# LV_cutoff.net
KiCad netlist of a schematic drawn in EAGLE
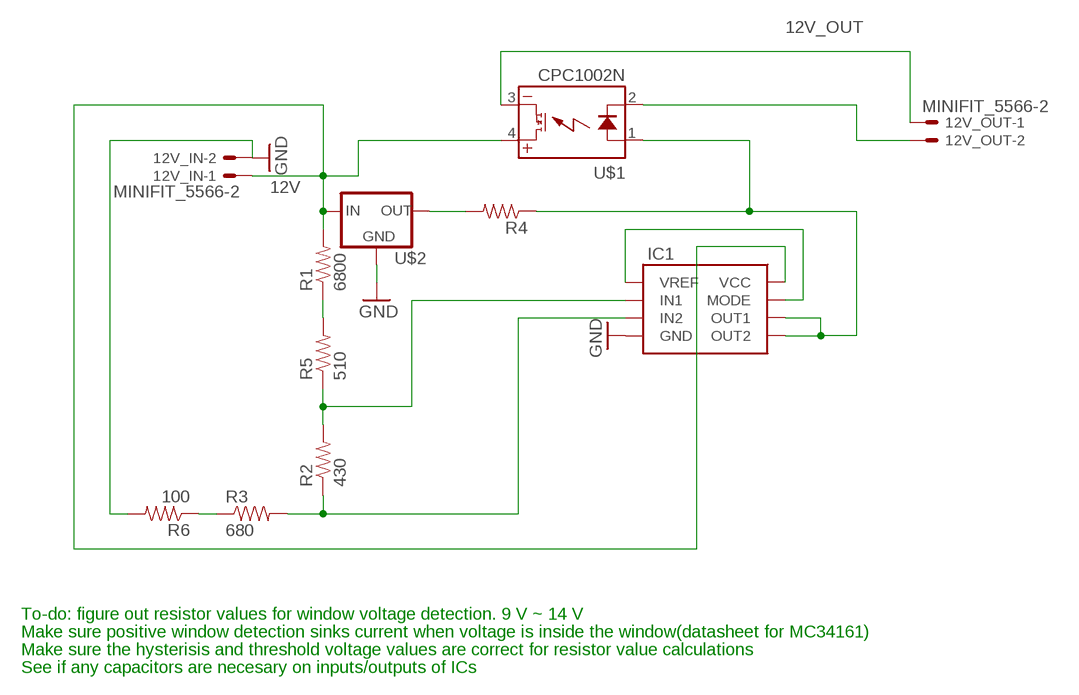
[diagram p0: schematic, sheet 1]

(export (version "E")
  (design (tool "Eeschema 10.0.6"))
  (components
    (comp (ref "12V_IN")
      (value "MINIFIT_5566-2")
      (footprint "eagle-import:MINIFIT_5566-2")
      (libsource (lib "eagle-import") (part "MINIFIT_5566-2"))
    )
    (comp (ref "12V_OUT")
      (value "MINIFIT_5566-2")
      (footprint "eagle-import:MINIFIT_5566-2")
      (libsource (lib "eagle-import") (part "MINIFIT_5566-2"))
    )
    (comp (ref "IC1")
      (value "MC34161DG")
      (footprint "eagle-import:SOIC-08")
      (libsource (lib "eagle-import") (part "MC34161DG"))
    )
    (comp (ref "R1")
      (value "6800")
      (footprint "eagle-import:0805")
      (libsource (lib "eagle-import") (part "RESISTOR0805-RES"))
    )
    (comp (ref "R2")
      (value "430")
      (footprint "eagle-import:0805")
      (libsource (lib "eagle-import") (part "RESISTOR0805-RES"))
    )
    (comp (ref "R3")
      (value "680")
      (footprint "eagle-import:0805")
      (libsource (lib "eagle-import") (part "RESISTOR0805-RES"))
    )
    (comp (ref "R4")
      (value "RESISTOR0805-RES")
      (footprint "eagle-import:0805")
      (libsource (lib "eagle-import") (part "RESISTOR0805-RES"))
    )
    (comp (ref "R5")
      (value "510")
      (footprint "eagle-import:0805")
      (libsource (lib "eagle-import") (part "RESISTOR0805-RES"))
    )
    (comp (ref "R6")
      (value "100")
      (footprint "eagle-import:0805")
      (libsource (lib "eagle-import") (part "RESISTOR0805-RES"))
    )
    (comp (ref "U$1")
      (value "CPC1002N")
      (footprint "eagle-import:SOP04")
      (libsource (lib "eagle-import") (part "CPC1002N"))
    )
    (comp (ref "U$2")
      (value "5VREG_LM340-NLM340MPX-5.0/NOPB")
      (footprint "eagle-import:SOT223")
      (libsource (lib "eagle-import") (part "5VREG_LM340-NLM340MPX-5.0/NOPB"))
    )
  )
  (nets
    (net (code "1") (name "/12V") (class "Default")
      (node (ref "12V_IN") (pin "1") (pinfunction "S_1") (pintype "passive"))
      (node (ref "IC1") (pin "8") (pinfunction "VCC_8") (pintype "passive"))
      (node (ref "R1") (pin "2") (pinfunction "2_2") (pintype "passive"))
      (node (ref "U$1") (pin "4") (pinfunction "DC+_4") (pintype "passive"))
      (node (ref "U$2") (pin "1") (pinfunction "IN_1") (pintype "input"))
    )
    (net (code "2") (name "/12V_OUT") (class "Default")
      (node (ref "12V_OUT") (pin "1") (pinfunction "S_1") (pintype "passive"))
      (node (ref "U$1") (pin "3") (pinfunction "DC-_3") (pintype "passive"))
    )
    (net (code "3") (name "GND") (class "Default")
      (node (ref "12V_IN") (pin "2") (pinfunction "S_2") (pintype "passive"))
      (node (ref "IC1") (pin "4") (pinfunction "GND_4") (pintype "passive"))
      (node (ref "R6") (pin "2") (pinfunction "2_2") (pintype "passive"))
      (node (ref "U$2") (pin "2") (pinfunction "GND_2") (pintype "input"))
      (node (ref "U$2") (pin "4") (pinfunction "GND_4") (pintype "input"))
    )
    (net (code "4") (name "Net-(12V_OUTB-S)") (class "Default")
      (node (ref "12V_OUT") (pin "2") (pinfunction "S_2") (pintype "passive"))
      (node (ref "U$1") (pin "2") (pinfunction "CONTROL-_2") (pintype "passive"))
    )
    (net (code "5") (name "Net-(IC1-IN1)") (class "Default")
      (node (ref "IC1") (pin "2") (pinfunction "IN1_2") (pintype "passive"))
      (node (ref "R2") (pin "2") (pinfunction "2_2") (pintype "passive"))
      (node (ref "R5") (pin "1") (pinfunction "1_1") (pintype "passive"))
    )
    (net (code "6") (name "Net-(IC1-IN2)") (class "Default")
      (node (ref "IC1") (pin "3") (pinfunction "IN2_3") (pintype "passive"))
      (node (ref "R2") (pin "1") (pinfunction "1_1") (pintype "passive"))
      (node (ref "R3") (pin "2") (pinfunction "2_2") (pintype "passive"))
    )
    (net (code "7") (name "Net-(IC1-MODE)") (class "Default")
      (node (ref "IC1") (pin "1") (pinfunction "VREF_1") (pintype "passive"))
      (node (ref "IC1") (pin "7") (pinfunction "MODE_7") (pintype "passive"))
    )
    (net (code "8") (name "Net-(IC1-OUT1)") (class "Default")
      (node (ref "IC1") (pin "5") (pinfunction "OUT2_5") (pintype "passive"))
      (node (ref "IC1") (pin "6") (pinfunction "OUT1_6") (pintype "passive"))
      (node (ref "R4") (pin "1") (pinfunction "1_1") (pintype "passive"))
      (node (ref "U$1") (pin "1") (pinfunction "CONTROL+_1") (pintype "passive"))
    )
    (net (code "9") (name "Net-(R1-Pad1)") (class "Default")
      (node (ref "R1") (pin "1") (pinfunction "1_1") (pintype "passive"))
      (node (ref "R5") (pin "2") (pinfunction "2_2") (pintype "passive"))
    )
    (net (code "10") (name "Net-(R3-Pad1)") (class "Default")
      (node (ref "R3") (pin "1") (pinfunction "1_1") (pintype "passive"))
      (node (ref "R6") (pin "1") (pinfunction "1_1") (pintype "passive"))
    )
    (net (code "11") (name "Net-(U$2-OUT)") (class "Default")
      (node (ref "R4") (pin "2") (pinfunction "2_2") (pintype "passive"))
      (node (ref "U$2") (pin "3") (pinfunction "OUT_3") (pintype "output"))
    )
  )
)
